# Core_Supply_Filter.net
KiCad netlist of a schematic drawn in Altium Designer
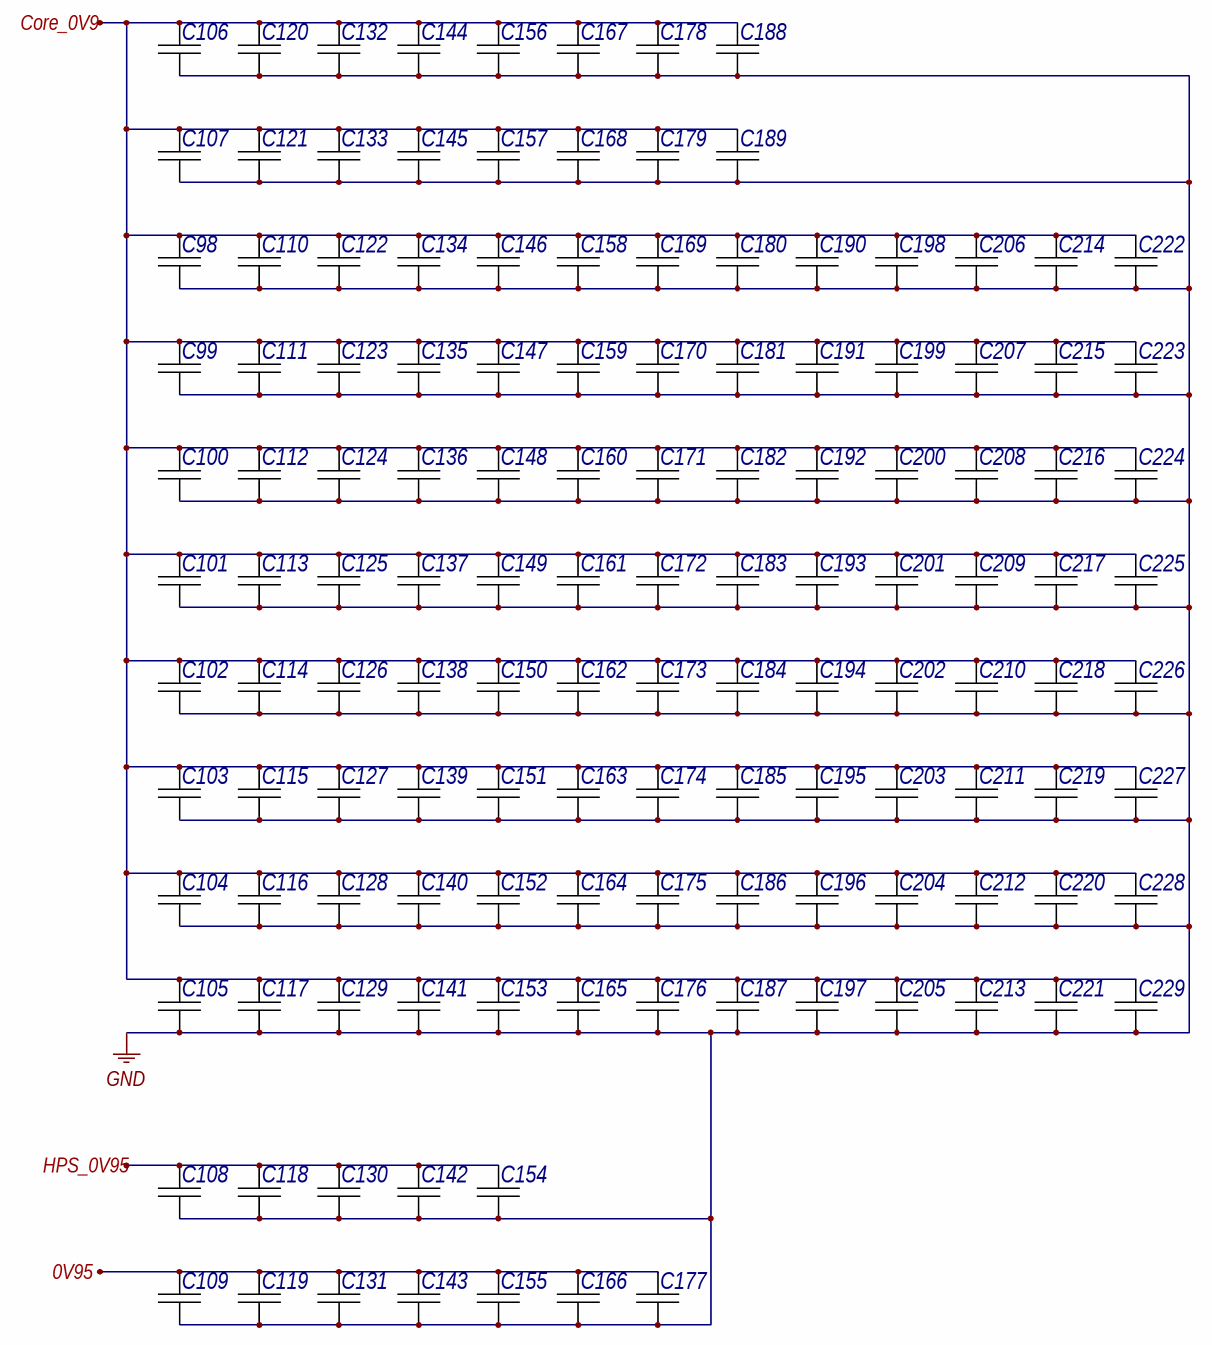
[diagram p0: Core Supply Filter.SchDoc]

(export (version "E")
  (design (tool "Eeschema 10.0.6"))
  (components
    (comp (ref "C98")
      (value "GRM033R60J104KE19D")
      (footprint "CAPC0603X33X15LL03T05")
      (description "Chip Capacitor, 100 nF, +/- 10%, 6.3 V, -55 to 85 degC, 0201 (0603 Metric), RoHS, Tape and Reel")
      (fields (field (name "TOLERANCE") "10%") (field (name "MANUFACTURER") "Basic Passives"))
      (libsource (lib "MiniPC DB") (part "CAP_NP"))
    )
    (comp (ref "C99")
      (value "GRM033R60J104KE19D")
      (footprint "CAPC0603X33X15LL03T05")
      (description "Chip Capacitor, 100 nF, +/- 10%, 6.3 V, -55 to 85 degC, 0201 (0603 Metric), RoHS, Tape and Reel")
      (fields (field (name "TOLERANCE") "10%") (field (name "MANUFACTURER") "Basic Passives"))
      (libsource (lib "MiniPC DB") (part "CAP_NP"))
    )
    (comp (ref "C100")
      (value "GRM033R60J104KE19D")
      (footprint "CAPC0603X33X15LL03T05")
      (description "Chip Capacitor, 100 nF, +/- 10%, 6.3 V, -55 to 85 degC, 0201 (0603 Metric), RoHS, Tape and Reel")
      (fields (field (name "TOLERANCE") "10%") (field (name "MANUFACTURER") "Basic Passives"))
      (libsource (lib "MiniPC DB") (part "CAP_NP"))
    )
    (comp (ref "C101")
      (value "GRM033R60J104KE19D")
      (footprint "CAPC0603X33X15LL03T05")
      (description "Chip Capacitor, 100 nF, +/- 10%, 6.3 V, -55 to 85 degC, 0201 (0603 Metric), RoHS, Tape and Reel")
      (fields (field (name "TOLERANCE") "10%") (field (name "MANUFACTURER") "Basic Passives"))
      (libsource (lib "MiniPC DB") (part "CAP_NP"))
    )
    (comp (ref "C102")
      (value "GRM033R60J104KE19D")
      (footprint "CAPC0603X33X15LL03T05")
      (description "Chip Capacitor, 100 nF, +/- 10%, 6.3 V, -55 to 85 degC, 0201 (0603 Metric), RoHS, Tape and Reel")
      (fields (field (name "TOLERANCE") "10%") (field (name "MANUFACTURER") "Basic Passives"))
      (libsource (lib "MiniPC DB") (part "CAP_NP"))
    )
    (comp (ref "C103")
      (value "GRM033R60J104KE19D")
      (footprint "CAPC0603X33X15LL03T05")
      (description "Chip Capacitor, 100 nF, +/- 10%, 6.3 V, -55 to 85 degC, 0201 (0603 Metric), RoHS, Tape and Reel")
      (fields (field (name "TOLERANCE") "10%") (field (name "MANUFACTURER") "Basic Passives"))
      (libsource (lib "MiniPC DB") (part "CAP_NP"))
    )
    (comp (ref "C104")
      (value "GRM033R60J104KE19D")
      (footprint "CAPC0603X33X15LL03T05")
      (description "Chip Capacitor, 100 nF, +/- 10%, 6.3 V, -55 to 85 degC, 0201 (0603 Metric), RoHS, Tape and Reel")
      (fields (field (name "TOLERANCE") "10%") (field (name "MANUFACTURER") "Basic Passives"))
      (libsource (lib "MiniPC DB") (part "CAP_NP"))
    )
    (comp (ref "C105")
      (value "GRM033R60J104KE19D")
      (footprint "CAPC0603X33X15LL03T05")
      (description "Chip Capacitor, 100 nF, +/- 10%, 6.3 V, -55 to 85 degC, 0201 (0603 Metric), RoHS, Tape and Reel")
      (fields (field (name "TOLERANCE") "10%") (field (name "MANUFACTURER") "Basic Passives"))
      (libsource (lib "MiniPC DB") (part "CAP_NP"))
    )
    (comp (ref "C106")
      (value "GRM31CR60J107ME39L")
      (footprint "CAPC3216X190X55ML30T25")
      (description "Chip Capacitor, 100 uF, +/- 20%, 6.3 V, -55 to 85 degC, 1206 (3216 Metric), RoHS, Tape and Reel")
      (fields (field (name "TOLERANCE") "20%"))
      (libsource (lib "MiniPC DB") (part "CAP_NP"))
    )
    (comp (ref "C107")
      (value "GRM31CR60J107ME39L")
      (footprint "CAPC3216X190X55ML30T25")
      (description "Chip Capacitor, 100 uF, +/- 20%, 6.3 V, -55 to 85 degC, 1206 (3216 Metric), RoHS, Tape and Reel")
      (fields (field (name "TOLERANCE") "20%"))
      (libsource (lib "MiniPC DB") (part "CAP_NP"))
    )
    (comp (ref "C108")
      (value "GRM31CR60J107ME39L")
      (footprint "CAPC3216X190X55ML30T25")
      (description "Chip Capacitor, 100 uF, +/- 20%, 6.3 V, -55 to 85 degC, 1206 (3216 Metric), RoHS, Tape and Reel")
      (fields (field (name "TOLERANCE") "20%"))
      (libsource (lib "MiniPC DB") (part "CAP_NP"))
    )
    (comp (ref "C109")
      (value "GRM31CR60J107ME39L")
      (footprint "CAPC3216X190X55ML30T25")
      (description "Chip Capacitor, 100 uF, +/- 20%, 6.3 V, -55 to 85 degC, 1206 (3216 Metric), RoHS, Tape and Reel")
      (fields (field (name "TOLERANCE") "20%"))
      (libsource (lib "MiniPC DB") (part "CAP_NP"))
    )
    (comp (ref "C110")
      (value "GRM033R60J104KE19D")
      (footprint "CAPC0603X33X15LL03T05")
      (description "Chip Capacitor, 100 nF, +/- 10%, 6.3 V, -55 to 85 degC, 0201 (0603 Metric), RoHS, Tape and Reel")
      (fields (field (name "TOLERANCE") "10%") (field (name "MANUFACTURER") "Basic Passives"))
      (libsource (lib "MiniPC DB") (part "CAP_NP"))
    )
    (comp (ref "C111")
      (value "GRM033R60J104KE19D")
      (footprint "CAPC0603X33X15LL03T05")
      (description "Chip Capacitor, 100 nF, +/- 10%, 6.3 V, -55 to 85 degC, 0201 (0603 Metric), RoHS, Tape and Reel")
      (fields (field (name "TOLERANCE") "10%") (field (name "MANUFACTURER") "Basic Passives"))
      (libsource (lib "MiniPC DB") (part "CAP_NP"))
    )
    (comp (ref "C112")
      (value "GRM033R60J104KE19D")
      (footprint "CAPC0603X33X15LL03T05")
      (description "Chip Capacitor, 100 nF, +/- 10%, 6.3 V, -55 to 85 degC, 0201 (0603 Metric), RoHS, Tape and Reel")
      (fields (field (name "TOLERANCE") "10%") (field (name "MANUFACTURER") "Basic Passives"))
      (libsource (lib "MiniPC DB") (part "CAP_NP"))
    )
    (comp (ref "C113")
      (value "GRM033R60J104KE19D")
      (footprint "CAPC0603X33X15LL03T05")
      (description "Chip Capacitor, 100 nF, +/- 10%, 6.3 V, -55 to 85 degC, 0201 (0603 Metric), RoHS, Tape and Reel")
      (fields (field (name "TOLERANCE") "10%") (field (name "MANUFACTURER") "Basic Passives"))
      (libsource (lib "MiniPC DB") (part "CAP_NP"))
    )
    (comp (ref "C114")
      (value "GRM033R60J104KE19D")
      (footprint "CAPC0603X33X15LL03T05")
      (description "Chip Capacitor, 100 nF, +/- 10%, 6.3 V, -55 to 85 degC, 0201 (0603 Metric), RoHS, Tape and Reel")
      (fields (field (name "TOLERANCE") "10%") (field (name "MANUFACTURER") "Basic Passives"))
      (libsource (lib "MiniPC DB") (part "CAP_NP"))
    )
    (comp (ref "C115")
      (value "GRM033R60J104KE19D")
      (footprint "CAPC0603X33X15LL03T05")
      (description "Chip Capacitor, 100 nF, +/- 10%, 6.3 V, -55 to 85 degC, 0201 (0603 Metric), RoHS, Tape and Reel")
      (fields (field (name "TOLERANCE") "10%") (field (name "MANUFACTURER") "Basic Passives"))
      (libsource (lib "MiniPC DB") (part "CAP_NP"))
    )
    (comp (ref "C116")
      (value "GRM033R60J104KE19D")
      (footprint "CAPC0603X33X15LL03T05")
      (description "Chip Capacitor, 100 nF, +/- 10%, 6.3 V, -55 to 85 degC, 0201 (0603 Metric), RoHS, Tape and Reel")
      (fields (field (name "TOLERANCE") "10%") (field (name "MANUFACTURER") "Basic Passives"))
      (libsource (lib "MiniPC DB") (part "CAP_NP"))
    )
    (comp (ref "C117")
      (value "GRM033R60J104KE19D")
      (footprint "CAPC0603X33X15LL03T05")
      (description "Chip Capacitor, 100 nF, +/- 10%, 6.3 V, -55 to 85 degC, 0201 (0603 Metric), RoHS, Tape and Reel")
      (fields (field (name "TOLERANCE") "10%") (field (name "MANUFACTURER") "Basic Passives"))
      (libsource (lib "MiniPC DB") (part "CAP_NP"))
    )
    (comp (ref "C118")
      (value "GRM033R60J104KE19D")
      (footprint "CAPC0603X33X15LL03T05")
      (description "Chip Capacitor, 100 nF, +/- 10%, 6.3 V, -55 to 85 degC, 0201 (0603 Metric), RoHS, Tape and Reel")
      (fields (field (name "TOLERANCE") "10%") (field (name "MANUFACTURER") "Basic Passives"))
      (libsource (lib "MiniPC DB") (part "CAP_NP"))
    )
    (comp (ref "C119")
      (value "GRM033R60J104KE19D")
      (footprint "CAPC0603X33X15LL03T05")
      (description "Chip Capacitor, 100 nF, +/- 10%, 6.3 V, -55 to 85 degC, 0201 (0603 Metric), RoHS, Tape and Reel")
      (fields (field (name "TOLERANCE") "10%") (field (name "MANUFACTURER") "Basic Passives"))
      (libsource (lib "MiniPC DB") (part "CAP_NP"))
    )
    (comp (ref "C120")
      (value "GRM31CR60J107ME39L")
      (footprint "CAPC3216X190X55ML30T25")
      (description "Chip Capacitor, 100 uF, +/- 20%, 6.3 V, -55 to 85 degC, 1206 (3216 Metric), RoHS, Tape and Reel")
      (fields (field (name "TOLERANCE") "20%"))
      (libsource (lib "MiniPC DB") (part "CAP_NP"))
    )
    (comp (ref "C121")
      (value "GRM31CR60J107ME39L")
      (footprint "CAPC3216X190X55ML30T25")
      (description "Chip Capacitor, 100 uF, +/- 20%, 6.3 V, -55 to 85 degC, 1206 (3216 Metric), RoHS, Tape and Reel")
      (fields (field (name "TOLERANCE") "20%"))
      (libsource (lib "MiniPC DB") (part "CAP_NP"))
    )
    (comp (ref "C122")
      (value "GRM033R60J104KE19D")
      (footprint "CAPC0603X33X15LL03T05")
      (description "Chip Capacitor, 100 nF, +/- 10%, 6.3 V, -55 to 85 degC, 0201 (0603 Metric), RoHS, Tape and Reel")
      (fields (field (name "TOLERANCE") "10%") (field (name "MANUFACTURER") "Basic Passives"))
      (libsource (lib "MiniPC DB") (part "CAP_NP"))
    )
    (comp (ref "C123")
      (value "GRM033R60J104KE19D")
      (footprint "CAPC0603X33X15LL03T05")
      (description "Chip Capacitor, 100 nF, +/- 10%, 6.3 V, -55 to 85 degC, 0201 (0603 Metric), RoHS, Tape and Reel")
      (fields (field (name "TOLERANCE") "10%") (field (name "MANUFACTURER") "Basic Passives"))
      (libsource (lib "MiniPC DB") (part "CAP_NP"))
    )
    (comp (ref "C124")
      (value "GRM033R60J104KE19D")
      (footprint "CAPC0603X33X15LL03T05")
      (description "Chip Capacitor, 100 nF, +/- 10%, 6.3 V, -55 to 85 degC, 0201 (0603 Metric), RoHS, Tape and Reel")
      (fields (field (name "TOLERANCE") "10%") (field (name "MANUFACTURER") "Basic Passives"))
      (libsource (lib "MiniPC DB") (part "CAP_NP"))
    )
    (comp (ref "C125")
      (value "GRM033R60J104KE19D")
      (footprint "CAPC0603X33X15LL03T05")
      (description "Chip Capacitor, 100 nF, +/- 10%, 6.3 V, -55 to 85 degC, 0201 (0603 Metric), RoHS, Tape and Reel")
      (fields (field (name "TOLERANCE") "10%") (field (name "MANUFACTURER") "Basic Passives"))
      (libsource (lib "MiniPC DB") (part "CAP_NP"))
    )
    (comp (ref "C126")
      (value "GRM033R60J104KE19D")
      (footprint "CAPC0603X33X15LL03T05")
      (description "Chip Capacitor, 100 nF, +/- 10%, 6.3 V, -55 to 85 degC, 0201 (0603 Metric), RoHS, Tape and Reel")
      (fields (field (name "TOLERANCE") "10%") (field (name "MANUFACTURER") "Basic Passives"))
      (libsource (lib "MiniPC DB") (part "CAP_NP"))
    )
    (comp (ref "C127")
      (value "GRM033R60J104KE19D")
      (footprint "CAPC0603X33X15LL03T05")
      (description "Chip Capacitor, 100 nF, +/- 10%, 6.3 V, -55 to 85 degC, 0201 (0603 Metric), RoHS, Tape and Reel")
      (fields (field (name "TOLERANCE") "10%") (field (name "MANUFACTURER") "Basic Passives"))
      (libsource (lib "MiniPC DB") (part "CAP_NP"))
    )
    (comp (ref "C128")
      (value "GRM033R60J104KE19D")
      (footprint "CAPC0603X33X15LL03T05")
      (description "Chip Capacitor, 100 nF, +/- 10%, 6.3 V, -55 to 85 degC, 0201 (0603 Metric), RoHS, Tape and Reel")
      (fields (field (name "TOLERANCE") "10%") (field (name "MANUFACTURER") "Basic Passives"))
      (libsource (lib "MiniPC DB") (part "CAP_NP"))
    )
    (comp (ref "C129")
      (value "GRM033R60J104KE19D")
      (footprint "CAPC0603X33X15LL03T05")
      (description "Chip Capacitor, 100 nF, +/- 10%, 6.3 V, -55 to 85 degC, 0201 (0603 Metric), RoHS, Tape and Reel")
      (fields (field (name "TOLERANCE") "10%") (field (name "MANUFACTURER") "Basic Passives"))
      (libsource (lib "MiniPC DB") (part "CAP_NP"))
    )
    (comp (ref "C130")
      (value "GRM033R60J104KE19D")
      (footprint "CAPC0603X33X15LL03T05")
      (description "Chip Capacitor, 100 nF, +/- 10%, 6.3 V, -55 to 85 degC, 0201 (0603 Metric), RoHS, Tape and Reel")
      (fields (field (name "TOLERANCE") "10%") (field (name "MANUFACTURER") "Basic Passives"))
      (libsource (lib "MiniPC DB") (part "CAP_NP"))
    )
    (comp (ref "C131")
      (value "GRM033R60J104KE19D")
      (footprint "CAPC0603X33X15LL03T05")
      (description "Chip Capacitor, 100 nF, +/- 10%, 6.3 V, -55 to 85 degC, 0201 (0603 Metric), RoHS, Tape and Reel")
      (fields (field (name "TOLERANCE") "10%") (field (name "MANUFACTURER") "Basic Passives"))
      (libsource (lib "MiniPC DB") (part "CAP_NP"))
    )
    (comp (ref "C132")
      (value "GRM31CR60J107ME39L")
      (footprint "CAPC3216X190X55ML30T25")
      (description "Chip Capacitor, 100 uF, +/- 20%, 6.3 V, -55 to 85 degC, 1206 (3216 Metric), RoHS, Tape and Reel")
      (fields (field (name "TOLERANCE") "20%"))
      (libsource (lib "MiniPC DB") (part "CAP_NP"))
    )
    (comp (ref "C133")
      (value "GRM31CR60J107ME39L")
      (footprint "CAPC3216X190X55ML30T25")
      (description "Chip Capacitor, 100 uF, +/- 20%, 6.3 V, -55 to 85 degC, 1206 (3216 Metric), RoHS, Tape and Reel")
      (fields (field (name "TOLERANCE") "20%"))
      (libsource (lib "MiniPC DB") (part "CAP_NP"))
    )
    (comp (ref "C134")
      (value "GRM033R60J104KE19D")
      (footprint "CAPC0603X33X15LL03T05")
      (description "Chip Capacitor, 100 nF, +/- 10%, 6.3 V, -55 to 85 degC, 0201 (0603 Metric), RoHS, Tape and Reel")
      (fields (field (name "TOLERANCE") "10%") (field (name "MANUFACTURER") "Basic Passives"))
      (libsource (lib "MiniPC DB") (part "CAP_NP"))
    )
    (comp (ref "C135")
      (value "GRM033R60J104KE19D")
      (footprint "CAPC0603X33X15LL03T05")
      (description "Chip Capacitor, 100 nF, +/- 10%, 6.3 V, -55 to 85 degC, 0201 (0603 Metric), RoHS, Tape and Reel")
      (fields (field (name "TOLERANCE") "10%") (field (name "MANUFACTURER") "Basic Passives"))
      (libsource (lib "MiniPC DB") (part "CAP_NP"))
    )
    (comp (ref "C136")
      (value "GRM033R60J104KE19D")
      (footprint "CAPC0603X33X15LL03T05")
      (description "Chip Capacitor, 100 nF, +/- 10%, 6.3 V, -55 to 85 degC, 0201 (0603 Metric), RoHS, Tape and Reel")
      (fields (field (name "TOLERANCE") "10%") (field (name "MANUFACTURER") "Basic Passives"))
      (libsource (lib "MiniPC DB") (part "CAP_NP"))
    )
    (comp (ref "C137")
      (value "GRM033R60J104KE19D")
      (footprint "CAPC0603X33X15LL03T05")
      (description "Chip Capacitor, 100 nF, +/- 10%, 6.3 V, -55 to 85 degC, 0201 (0603 Metric), RoHS, Tape and Reel")
      (fields (field (name "TOLERANCE") "10%") (field (name "MANUFACTURER") "Basic Passives"))
      (libsource (lib "MiniPC DB") (part "CAP_NP"))
    )
    (comp (ref "C138")
      (value "GRM033R60J104KE19D")
      (footprint "CAPC0603X33X15LL03T05")
      (description "Chip Capacitor, 100 nF, +/- 10%, 6.3 V, -55 to 85 degC, 0201 (0603 Metric), RoHS, Tape and Reel")
      (fields (field (name "TOLERANCE") "10%") (field (name "MANUFACTURER") "Basic Passives"))
      (libsource (lib "MiniPC DB") (part "CAP_NP"))
    )
    (comp (ref "C139")
      (value "GRM033R60J104KE19D")
      (footprint "CAPC0603X33X15LL03T05")
      (description "Chip Capacitor, 100 nF, +/- 10%, 6.3 V, -55 to 85 degC, 0201 (0603 Metric), RoHS, Tape and Reel")
      (fields (field (name "TOLERANCE") "10%") (field (name "MANUFACTURER") "Basic Passives"))
      (libsource (lib "MiniPC DB") (part "CAP_NP"))
    )
    (comp (ref "C140")
      (value "GRM033R60J104KE19D")
      (footprint "CAPC0603X33X15LL03T05")
      (description "Chip Capacitor, 100 nF, +/- 10%, 6.3 V, -55 to 85 degC, 0201 (0603 Metric), RoHS, Tape and Reel")
      (fields (field (name "TOLERANCE") "10%") (field (name "MANUFACTURER") "Basic Passives"))
      (libsource (lib "MiniPC DB") (part "CAP_NP"))
    )
    (comp (ref "C141")
      (value "GRM033R60J104KE19D")
      (footprint "CAPC0603X33X15LL03T05")
      (description "Chip Capacitor, 100 nF, +/- 10%, 6.3 V, -55 to 85 degC, 0201 (0603 Metric), RoHS, Tape and Reel")
      (fields (field (name "TOLERANCE") "10%") (field (name "MANUFACTURER") "Basic Passives"))
      (libsource (lib "MiniPC DB") (part "CAP_NP"))
    )
    (comp (ref "C142")
      (value "GRM033R60J104KE19D")
      (footprint "CAPC0603X33X15LL03T05")
      (description "Chip Capacitor, 100 nF, +/- 10%, 6.3 V, -55 to 85 degC, 0201 (0603 Metric), RoHS, Tape and Reel")
      (fields (field (name "TOLERANCE") "10%") (field (name "MANUFACTURER") "Basic Passives"))
      (libsource (lib "MiniPC DB") (part "CAP_NP"))
    )
    (comp (ref "C143")
      (value "GRM033R60J104KE19D")
      (footprint "CAPC0603X33X15LL03T05")
      (description "Chip Capacitor, 100 nF, +/- 10%, 6.3 V, -55 to 85 degC, 0201 (0603 Metric), RoHS, Tape and Reel")
      (fields (field (name "TOLERANCE") "10%") (field (name "MANUFACTURER") "Basic Passives"))
      (libsource (lib "MiniPC DB") (part "CAP_NP"))
    )
    (comp (ref "C144")
      (value "GRM31CR60J107ME39L")
      (footprint "CAPC3216X190X55ML30T25")
      (description "Chip Capacitor, 100 uF, +/- 20%, 6.3 V, -55 to 85 degC, 1206 (3216 Metric), RoHS, Tape and Reel")
      (fields (field (name "TOLERANCE") "20%"))
      (libsource (lib "MiniPC DB") (part "CAP_NP"))
    )
    (comp (ref "C145")
      (value "GRM31CR60J107ME39L")
      (footprint "CAPC3216X190X55ML30T25")
      (description "Chip Capacitor, 100 uF, +/- 20%, 6.3 V, -55 to 85 degC, 1206 (3216 Metric), RoHS, Tape and Reel")
      (fields (field (name "TOLERANCE") "20%"))
      (libsource (lib "MiniPC DB") (part "CAP_NP"))
    )
    (comp (ref "C146")
      (value "GRM033R60J104KE19D")
      (footprint "CAPC0603X33X15LL03T05")
      (description "Chip Capacitor, 100 nF, +/- 10%, 6.3 V, -55 to 85 degC, 0201 (0603 Metric), RoHS, Tape and Reel")
      (fields (field (name "TOLERANCE") "10%") (field (name "MANUFACTURER") "Basic Passives"))
      (libsource (lib "MiniPC DB") (part "CAP_NP"))
    )
    (comp (ref "C147")
      (value "GRM033R60J104KE19D")
      (footprint "CAPC0603X33X15LL03T05")
      (description "Chip Capacitor, 100 nF, +/- 10%, 6.3 V, -55 to 85 degC, 0201 (0603 Metric), RoHS, Tape and Reel")
      (fields (field (name "TOLERANCE") "10%") (field (name "MANUFACTURER") "Basic Passives"))
      (libsource (lib "MiniPC DB") (part "CAP_NP"))
    )
    (comp (ref "C148")
      (value "GRM033R60J104KE19D")
      (footprint "CAPC0603X33X15LL03T05")
      (description "Chip Capacitor, 100 nF, +/- 10%, 6.3 V, -55 to 85 degC, 0201 (0603 Metric), RoHS, Tape and Reel")
      (fields (field (name "TOLERANCE") "10%") (field (name "MANUFACTURER") "Basic Passives"))
      (libsource (lib "MiniPC DB") (part "CAP_NP"))
    )
    (comp (ref "C149")
      (value "GRM033R60J104KE19D")
      (footprint "CAPC0603X33X15LL03T05")
      (description "Chip Capacitor, 100 nF, +/- 10%, 6.3 V, -55 to 85 degC, 0201 (0603 Metric), RoHS, Tape and Reel")
      (fields (field (name "TOLERANCE") "10%") (field (name "MANUFACTURER") "Basic Passives"))
      (libsource (lib "MiniPC DB") (part "CAP_NP"))
    )
    (comp (ref "C150")
      (value "GRM033R60J104KE19D")
      (footprint "CAPC0603X33X15LL03T05")
      (description "Chip Capacitor, 100 nF, +/- 10%, 6.3 V, -55 to 85 degC, 0201 (0603 Metric), RoHS, Tape and Reel")
      (fields (field (name "TOLERANCE") "10%") (field (name "MANUFACTURER") "Basic Passives"))
      (libsource (lib "MiniPC DB") (part "CAP_NP"))
    )
    (comp (ref "C151")
      (value "GRM033R60J104KE19D")
      (footprint "CAPC0603X33X15LL03T05")
      (description "Chip Capacitor, 100 nF, +/- 10%, 6.3 V, -55 to 85 degC, 0201 (0603 Metric), RoHS, Tape and Reel")
      (fields (field (name "TOLERANCE") "10%") (field (name "MANUFACTURER") "Basic Passives"))
      (libsource (lib "MiniPC DB") (part "CAP_NP"))
    )
    (comp (ref "C152")
      (value "GRM033R60J104KE19D")
      (footprint "CAPC0603X33X15LL03T05")
      (description "Chip Capacitor, 100 nF, +/- 10%, 6.3 V, -55 to 85 degC, 0201 (0603 Metric), RoHS, Tape and Reel")
      (fields (field (name "TOLERANCE") "10%") (field (name "MANUFACTURER") "Basic Passives"))
      (libsource (lib "MiniPC DB") (part "CAP_NP"))
    )
    (comp (ref "C153")
      (value "GRM033R60J104KE19D")
      (footprint "CAPC0603X33X15LL03T05")
      (description "Chip Capacitor, 100 nF, +/- 10%, 6.3 V, -55 to 85 degC, 0201 (0603 Metric), RoHS, Tape and Reel")
      (fields (field (name "TOLERANCE") "10%") (field (name "MANUFACTURER") "Basic Passives"))
      (libsource (lib "MiniPC DB") (part "CAP_NP"))
    )
    (comp (ref "C154")
      (value "GRM033R60J104KE19D")
      (footprint "CAPC0603X33X15LL03T05")
      (description "Chip Capacitor, 100 nF, +/- 10%, 6.3 V, -55 to 85 degC, 0201 (0603 Metric), RoHS, Tape and Reel")
      (fields (field (name "TOLERANCE") "10%") (field (name "MANUFACTURER") "Basic Passives"))
      (libsource (lib "MiniPC DB") (part "CAP_NP"))
    )
    (comp (ref "C155")
      (value "GRM033R60J104KE19D")
      (footprint "CAPC0603X33X15LL03T05")
      (description "Chip Capacitor, 100 nF, +/- 10%, 6.3 V, -55 to 85 degC, 0201 (0603 Metric), RoHS, Tape and Reel")
      (fields (field (name "TOLERANCE") "10%") (field (name "MANUFACTURER") "Basic Passives"))
      (libsource (lib "MiniPC DB") (part "CAP_NP"))
    )
    (comp (ref "C156")
      (value "GRM31CR60J107ME39L")
      (footprint "CAPC3216X190X55ML30T25")
      (description "Chip Capacitor, 100 uF, +/- 20%, 6.3 V, -55 to 85 degC, 1206 (3216 Metric), RoHS, Tape and Reel")
      (fields (field (name "TOLERANCE") "20%"))
      (libsource (lib "MiniPC DB") (part "CAP_NP"))
    )
    (comp (ref "C157")
      (value "GRM31CR60J107ME39L")
      (footprint "CAPC3216X190X55ML30T25")
      (description "Chip Capacitor, 100 uF, +/- 20%, 6.3 V, -55 to 85 degC, 1206 (3216 Metric), RoHS, Tape and Reel")
      (fields (field (name "TOLERANCE") "20%"))
      (libsource (lib "MiniPC DB") (part "CAP_NP"))
    )
    (comp (ref "C158")
      (value "GRM033R60J104KE19D")
      (footprint "CAPC0603X33X15LL03T05")
      (description "Chip Capacitor, 100 nF, +/- 10%, 6.3 V, -55 to 85 degC, 0201 (0603 Metric), RoHS, Tape and Reel")
      (fields (field (name "TOLERANCE") "10%") (field (name "MANUFACTURER") "Basic Passives"))
      (libsource (lib "MiniPC DB") (part "CAP_NP"))
    )
    (comp (ref "C159")
      (value "GRM033R60J104KE19D")
      (footprint "CAPC0603X33X15LL03T05")
      (description "Chip Capacitor, 100 nF, +/- 10%, 6.3 V, -55 to 85 degC, 0201 (0603 Metric), RoHS, Tape and Reel")
      (fields (field (name "TOLERANCE") "10%") (field (name "MANUFACTURER") "Basic Passives"))
      (libsource (lib "MiniPC DB") (part "CAP_NP"))
    )
    (comp (ref "C160")
      (value "GRM033R60J104KE19D")
      (footprint "CAPC0603X33X15LL03T05")
      (description "Chip Capacitor, 100 nF, +/- 10%, 6.3 V, -55 to 85 degC, 0201 (0603 Metric), RoHS, Tape and Reel")
      (fields (field (name "TOLERANCE") "10%") (field (name "MANUFACTURER") "Basic Passives"))
      (libsource (lib "MiniPC DB") (part "CAP_NP"))
    )
    (comp (ref "C161")
      (value "GRM033R60J104KE19D")
      (footprint "CAPC0603X33X15LL03T05")
      (description "Chip Capacitor, 100 nF, +/- 10%, 6.3 V, -55 to 85 degC, 0201 (0603 Metric), RoHS, Tape and Reel")
      (fields (field (name "TOLERANCE") "10%") (field (name "MANUFACTURER") "Basic Passives"))
      (libsource (lib "MiniPC DB") (part "CAP_NP"))
    )
    (comp (ref "C162")
      (value "GRM033R60J104KE19D")
      (footprint "CAPC0603X33X15LL03T05")
      (description "Chip Capacitor, 100 nF, +/- 10%, 6.3 V, -55 to 85 degC, 0201 (0603 Metric), RoHS, Tape and Reel")
      (fields (field (name "TOLERANCE") "10%") (field (name "MANUFACTURER") "Basic Passives"))
      (libsource (lib "MiniPC DB") (part "CAP_NP"))
    )
    (comp (ref "C163")
      (value "GRM033R60J104KE19D")
      (footprint "CAPC0603X33X15LL03T05")
      (description "Chip Capacitor, 100 nF, +/- 10%, 6.3 V, -55 to 85 degC, 0201 (0603 Metric), RoHS, Tape and Reel")
      (fields (field (name "TOLERANCE") "10%") (field (name "MANUFACTURER") "Basic Passives"))
      (libsource (lib "MiniPC DB") (part "CAP_NP"))
    )
    (comp (ref "C164")
      (value "GRM033R60J104KE19D")
      (footprint "CAPC0603X33X15LL03T05")
      (description "Chip Capacitor, 100 nF, +/- 10%, 6.3 V, -55 to 85 degC, 0201 (0603 Metric), RoHS, Tape and Reel")
      (fields (field (name "TOLERANCE") "10%") (field (name "MANUFACTURER") "Basic Passives"))
      (libsource (lib "MiniPC DB") (part "CAP_NP"))
    )
    (comp (ref "C165")
      (value "GRM033R60J104KE19D")
      (footprint "CAPC0603X33X15LL03T05")
      (description "Chip Capacitor, 100 nF, +/- 10%, 6.3 V, -55 to 85 degC, 0201 (0603 Metric), RoHS, Tape and Reel")
      (fields (field (name "TOLERANCE") "10%") (field (name "MANUFACTURER") "Basic Passives"))
      (libsource (lib "MiniPC DB") (part "CAP_NP"))
    )
    (comp (ref "C166")
      (value "GRM033R60J104KE19D")
      (footprint "CAPC0603X33X15LL03T05")
      (description "Chip Capacitor, 100 nF, +/- 10%, 6.3 V, -55 to 85 degC, 0201 (0603 Metric), RoHS, Tape and Reel")
      (fields (field (name "TOLERANCE") "10%") (field (name "MANUFACTURER") "Basic Passives"))
      (libsource (lib "MiniPC DB") (part "CAP_NP"))
    )
    (comp (ref "C167")
      (value "GRM31CR60J107ME39L")
      (footprint "CAPC3216X190X55ML30T25")
      (description "Chip Capacitor, 100 uF, +/- 20%, 6.3 V, -55 to 85 degC, 1206 (3216 Metric), RoHS, Tape and Reel")
      (fields (field (name "TOLERANCE") "20%"))
      (libsource (lib "MiniPC DB") (part "CAP_NP"))
    )
    (comp (ref "C168")
      (value "GRM31CR60J107ME39L")
      (footprint "CAPC3216X190X55ML30T25")
      (description "Chip Capacitor, 100 uF, +/- 20%, 6.3 V, -55 to 85 degC, 1206 (3216 Metric), RoHS, Tape and Reel")
      (fields (field (name "TOLERANCE") "20%"))
      (libsource (lib "MiniPC DB") (part "CAP_NP"))
    )
    (comp (ref "C169")
      (value "GRM033R60J104KE19D")
      (footprint "CAPC0603X33X15LL03T05")
      (description "Chip Capacitor, 100 nF, +/- 10%, 6.3 V, -55 to 85 degC, 0201 (0603 Metric), RoHS, Tape and Reel")
      (fields (field (name "TOLERANCE") "10%") (field (name "MANUFACTURER") "Basic Passives"))
      (libsource (lib "MiniPC DB") (part "CAP_NP"))
    )
    (comp (ref "C170")
      (value "GRM033R60J104KE19D")
      (footprint "CAPC0603X33X15LL03T05")
      (description "Chip Capacitor, 100 nF, +/- 10%, 6.3 V, -55 to 85 degC, 0201 (0603 Metric), RoHS, Tape and Reel")
      (fields (field (name "TOLERANCE") "10%") (field (name "MANUFACTURER") "Basic Passives"))
      (libsource (lib "MiniPC DB") (part "CAP_NP"))
    )
    (comp (ref "C171")
      (value "GRM033R60J104KE19D")
      (footprint "CAPC0603X33X15LL03T05")
      (description "Chip Capacitor, 100 nF, +/- 10%, 6.3 V, -55 to 85 degC, 0201 (0603 Metric), RoHS, Tape and Reel")
      (fields (field (name "TOLERANCE") "10%") (field (name "MANUFACTURER") "Basic Passives"))
      (libsource (lib "MiniPC DB") (part "CAP_NP"))
    )
    (comp (ref "C172")
      (value "GRM033R60J104KE19D")
      (footprint "CAPC0603X33X15LL03T05")
      (description "Chip Capacitor, 100 nF, +/- 10%, 6.3 V, -55 to 85 degC, 0201 (0603 Metric), RoHS, Tape and Reel")
      (fields (field (name "TOLERANCE") "10%") (field (name "MANUFACTURER") "Basic Passives"))
      (libsource (lib "MiniPC DB") (part "CAP_NP"))
    )
    (comp (ref "C173")
      (value "GRM033R60J104KE19D")
      (footprint "CAPC0603X33X15LL03T05")
      (description "Chip Capacitor, 100 nF, +/- 10%, 6.3 V, -55 to 85 degC, 0201 (0603 Metric), RoHS, Tape and Reel")
      (fields (field (name "TOLERANCE") "10%") (field (name "MANUFACTURER") "Basic Passives"))
      (libsource (lib "MiniPC DB") (part "CAP_NP"))
    )
    (comp (ref "C174")
      (value "GRM033R60J104KE19D")
      (footprint "CAPC0603X33X15LL03T05")
      (description "Chip Capacitor, 100 nF, +/- 10%, 6.3 V, -55 to 85 degC, 0201 (0603 Metric), RoHS, Tape and Reel")
      (fields (field (name "TOLERANCE") "10%") (field (name "MANUFACTURER") "Basic Passives"))
      (libsource (lib "MiniPC DB") (part "CAP_NP"))
    )
    (comp (ref "C175")
      (value "GRM033R60J104KE19D")
      (footprint "CAPC0603X33X15LL03T05")
      (description "Chip Capacitor, 100 nF, +/- 10%, 6.3 V, -55 to 85 degC, 0201 (0603 Metric), RoHS, Tape and Reel")
      (fields (field (name "TOLERANCE") "10%") (field (name "MANUFACTURER") "Basic Passives"))
      (libsource (lib "MiniPC DB") (part "CAP_NP"))
    )
    (comp (ref "C176")
      (value "GRM033R60J104KE19D")
      (footprint "CAPC0603X33X15LL03T05")
      (description "Chip Capacitor, 100 nF, +/- 10%, 6.3 V, -55 to 85 degC, 0201 (0603 Metric), RoHS, Tape and Reel")
      (fields (field (name "TOLERANCE") "10%") (field (name "MANUFACTURER") "Basic Passives"))
      (libsource (lib "MiniPC DB") (part "CAP_NP"))
    )
    (comp (ref "C177")
      (value "GRM033R60J104KE19D")
      (footprint "CAPC0603X33X15LL03T05")
      (description "Chip Capacitor, 100 nF, +/- 10%, 6.3 V, -55 to 85 degC, 0201 (0603 Metric), RoHS, Tape and Reel")
      (fields (field (name "TOLERANCE") "10%") (field (name "MANUFACTURER") "Basic Passives"))
      (libsource (lib "MiniPC DB") (part "CAP_NP"))
    )
    (comp (ref "C178")
      (value "GRM31CR60J107ME39L")
      (footprint "CAPC3216X190X55ML30T25")
      (description "Chip Capacitor, 100 uF, +/- 20%, 6.3 V, -55 to 85 degC, 1206 (3216 Metric), RoHS, Tape and Reel")
      (fields (field (name "TOLERANCE") "20%"))
      (libsource (lib "MiniPC DB") (part "CAP_NP"))
    )
    (comp (ref "C179")
      (value "GRM31CR60J107ME39L")
      (footprint "CAPC3216X190X55ML30T25")
      (description "Chip Capacitor, 100 uF, +/- 20%, 6.3 V, -55 to 85 degC, 1206 (3216 Metric), RoHS, Tape and Reel")
      (fields (field (name "TOLERANCE") "20%"))
      (libsource (lib "MiniPC DB") (part "CAP_NP"))
    )
    (comp (ref "C180")
      (value "GRM033R60J104KE19D")
      (footprint "CAPC0603X33X15LL03T05")
      (description "Chip Capacitor, 100 nF, +/- 10%, 6.3 V, -55 to 85 degC, 0201 (0603 Metric), RoHS, Tape and Reel")
      (fields (field (name "TOLERANCE") "10%") (field (name "MANUFACTURER") "Basic Passives"))
      (libsource (lib "MiniPC DB") (part "CAP_NP"))
    )
    (comp (ref "C181")
      (value "GRM033R60J104KE19D")
      (footprint "CAPC0603X33X15LL03T05")
      (description "Chip Capacitor, 100 nF, +/- 10%, 6.3 V, -55 to 85 degC, 0201 (0603 Metric), RoHS, Tape and Reel")
      (fields (field (name "TOLERANCE") "10%") (field (name "MANUFACTURER") "Basic Passives"))
      (libsource (lib "MiniPC DB") (part "CAP_NP"))
    )
    (comp (ref "C182")
      (value "GRM033R60J104KE19D")
      (footprint "CAPC0603X33X15LL03T05")
      (description "Chip Capacitor, 100 nF, +/- 10%, 6.3 V, -55 to 85 degC, 0201 (0603 Metric), RoHS, Tape and Reel")
      (fields (field (name "TOLERANCE") "10%") (field (name "MANUFACTURER") "Basic Passives"))
      (libsource (lib "MiniPC DB") (part "CAP_NP"))
    )
    (comp (ref "C183")
      (value "GRM033R60J104KE19D")
      (footprint "CAPC0603X33X15LL03T05")
      (description "Chip Capacitor, 100 nF, +/- 10%, 6.3 V, -55 to 85 degC, 0201 (0603 Metric), RoHS, Tape and Reel")
      (fields (field (name "TOLERANCE") "10%") (field (name "MANUFACTURER") "Basic Passives"))
      (libsource (lib "MiniPC DB") (part "CAP_NP"))
    )
    (comp (ref "C184")
      (value "GRM033R60J104KE19D")
      (footprint "CAPC0603X33X15LL03T05")
      (description "Chip Capacitor, 100 nF, +/- 10%, 6.3 V, -55 to 85 degC, 0201 (0603 Metric), RoHS, Tape and Reel")
      (fields (field (name "TOLERANCE") "10%") (field (name "MANUFACTURER") "Basic Passives"))
      (libsource (lib "MiniPC DB") (part "CAP_NP"))
    )
    (comp (ref "C185")
      (value "GRM033R60J104KE19D")
      (footprint "CAPC0603X33X15LL03T05")
      (description "Chip Capacitor, 100 nF, +/- 10%, 6.3 V, -55 to 85 degC, 0201 (0603 Metric), RoHS, Tape and Reel")
      (fields (field (name "TOLERANCE") "10%") (field (name "MANUFACTURER") "Basic Passives"))
      (libsource (lib "MiniPC DB") (part "CAP_NP"))
    )
    (comp (ref "C186")
      (value "GRM033R60J104KE19D")
      (footprint "CAPC0603X33X15LL03T05")
      (description "Chip Capacitor, 100 nF, +/- 10%, 6.3 V, -55 to 85 degC, 0201 (0603 Metric), RoHS, Tape and Reel")
      (fields (field (name "TOLERANCE") "10%") (field (name "MANUFACTURER") "Basic Passives"))
      (libsource (lib "MiniPC DB") (part "CAP_NP"))
    )
    (comp (ref "C187")
      (value "GRM033R60J104KE19D")
      (footprint "CAPC0603X33X15LL03T05")
      (description "Chip Capacitor, 100 nF, +/- 10%, 6.3 V, -55 to 85 degC, 0201 (0603 Metric), RoHS, Tape and Reel")
      (fields (field (name "TOLERANCE") "10%") (field (name "MANUFACTURER") "Basic Passives"))
      (libsource (lib "MiniPC DB") (part "CAP_NP"))
    )
    (comp (ref "C188")
      (value "GRM31CR60J107ME39L")
      (footprint "CAPC3216X190X55ML30T25")
      (description "Chip Capacitor, 100 uF, +/- 20%, 6.3 V, -55 to 85 degC, 1206 (3216 Metric), RoHS, Tape and Reel")
      (fields (field (name "TOLERANCE") "20%"))
      (libsource (lib "MiniPC DB") (part "CAP_NP"))
    )
    (comp (ref "C189")
      (value "GRM31CR60J107ME39L")
      (footprint "CAPC3216X190X55ML30T25")
      (description "Chip Capacitor, 100 uF, +/- 20%, 6.3 V, -55 to 85 degC, 1206 (3216 Metric), RoHS, Tape and Reel")
      (fields (field (name "TOLERANCE") "20%"))
      (libsource (lib "MiniPC DB") (part "CAP_NP"))
    )
    (comp (ref "C190")
      (value "GRM033R60J104KE19D")
      (footprint "CAPC0603X33X15LL03T05")
      (description "Chip Capacitor, 100 nF, +/- 10%, 6.3 V, -55 to 85 degC, 0201 (0603 Metric), RoHS, Tape and Reel")
      (fields (field (name "TOLERANCE") "10%") (field (name "MANUFACTURER") "Basic Passives"))
      (libsource (lib "MiniPC DB") (part "CAP_NP"))
    )
    (comp (ref "C191")
      (value "GRM033R60J104KE19D")
      (footprint "CAPC0603X33X15LL03T05")
      (description "Chip Capacitor, 100 nF, +/- 10%, 6.3 V, -55 to 85 degC, 0201 (0603 Metric), RoHS, Tape and Reel")
      (fields (field (name "TOLERANCE") "10%") (field (name "MANUFACTURER") "Basic Passives"))
      (libsource (lib "MiniPC DB") (part "CAP_NP"))
    )
    (comp (ref "C192")
      (value "GRM033R60J104KE19D")
      (footprint "CAPC0603X33X15LL03T05")
      (description "Chip Capacitor, 100 nF, +/- 10%, 6.3 V, -55 to 85 degC, 0201 (0603 Metric), RoHS, Tape and Reel")
      (fields (field (name "TOLERANCE") "10%") (field (name "MANUFACTURER") "Basic Passives"))
      (libsource (lib "MiniPC DB") (part "CAP_NP"))
    )
    (comp (ref "C193")
      (value "GRM033R60J104KE19D")
      (footprint "CAPC0603X33X15LL03T05")
      (description "Chip Capacitor, 100 nF, +/- 10%, 6.3 V, -55 to 85 degC, 0201 (0603 Metric), RoHS, Tape and Reel")
      (fields (field (name "TOLERANCE") "10%") (field (name "MANUFACTURER") "Basic Passives"))
      (libsource (lib "MiniPC DB") (part "CAP_NP"))
    )
    (comp (ref "C194")
      (value "GRM033R60J104KE19D")
      (footprint "CAPC0603X33X15LL03T05")
      (description "Chip Capacitor, 100 nF, +/- 10%, 6.3 V, -55 to 85 degC, 0201 (0603 Metric), RoHS, Tape and Reel")
      (fields (field (name "TOLERANCE") "10%") (field (name "MANUFACTURER") "Basic Passives"))
      (libsource (lib "MiniPC DB") (part "CAP_NP"))
    )
    (comp (ref "C195")
      (value "GRM033R60J104KE19D")
      (footprint "CAPC0603X33X15LL03T05")
      (description "Chip Capacitor, 100 nF, +/- 10%, 6.3 V, -55 to 85 degC, 0201 (0603 Metric), RoHS, Tape and Reel")
      (fields (field (name "TOLERANCE") "10%") (field (name "MANUFACTURER") "Basic Passives"))
      (libsource (lib "MiniPC DB") (part "CAP_NP"))
    )
    (comp (ref "C196")
      (value "GRM033R60J104KE19D")
      (footprint "CAPC0603X33X15LL03T05")
      (description "Chip Capacitor, 100 nF, +/- 10%, 6.3 V, -55 to 85 degC, 0201 (0603 Metric), RoHS, Tape and Reel")
      (fields (field (name "TOLERANCE") "10%") (field (name "MANUFACTURER") "Basic Passives"))
      (libsource (lib "MiniPC DB") (part "CAP_NP"))
    )
    (comp (ref "C197")
      (value "GRM033R60J104KE19D")
      (footprint "CAPC0603X33X15LL03T05")
      (description "Chip Capacitor, 100 nF, +/- 10%, 6.3 V, -55 to 85 degC, 0201 (0603 Metric), RoHS, Tape and Reel")
      (fields (field (name "TOLERANCE") "10%") (field (name "MANUFACTURER") "Basic Passives"))
      (libsource (lib "MiniPC DB") (part "CAP_NP"))
    )
    (comp (ref "C198")
      (value "GRM033R60J104KE19D")
      (footprint "CAPC0603X33X15LL03T05")
      (description "Chip Capacitor, 100 nF, +/- 10%, 6.3 V, -55 to 85 degC, 0201 (0603 Metric), RoHS, Tape and Reel")
      (fields (field (name "TOLERANCE") "10%") (field (name "MANUFACTURER") "Basic Passives"))
      (libsource (lib "MiniPC DB") (part "CAP_NP"))
    )
    (comp (ref "C199")
      (value "GRM033R60J104KE19D")
      (footprint "CAPC0603X33X15LL03T05")
      (description "Chip Capacitor, 100 nF, +/- 10%, 6.3 V, -55 to 85 degC, 0201 (0603 Metric), RoHS, Tape and Reel")
      (fields (field (name "TOLERANCE") "10%") (field (name "MANUFACTURER") "Basic Passives"))
      (libsource (lib "MiniPC DB") (part "CAP_NP"))
    )
    (comp (ref "C200")
      (value "GRM033R60J104KE19D")
      (footprint "CAPC0603X33X15LL03T05")
      (description "Chip Capacitor, 100 nF, +/- 10%, 6.3 V, -55 to 85 degC, 0201 (0603 Metric), RoHS, Tape and Reel")
      (fields (field (name "TOLERANCE") "10%") (field (name "MANUFACTURER") "Basic Passives"))
      (libsource (lib "MiniPC DB") (part "CAP_NP"))
    )
    (comp (ref "C201")
      (value "GRM033R60J104KE19D")
      (footprint "CAPC0603X33X15LL03T05")
      (description "Chip Capacitor, 100 nF, +/- 10%, 6.3 V, -55 to 85 degC, 0201 (0603 Metric), RoHS, Tape and Reel")
      (fields (field (name "TOLERANCE") "10%") (field (name "MANUFACTURER") "Basic Passives"))
      (libsource (lib "MiniPC DB") (part "CAP_NP"))
    )
    (comp (ref "C202")
      (value "GRM033R60J104KE19D")
      (footprint "CAPC0603X33X15LL03T05")
      (description "Chip Capacitor, 100 nF, +/- 10%, 6.3 V, -55 to 85 degC, 0201 (0603 Metric), RoHS, Tape and Reel")
      (fields (field (name "TOLERANCE") "10%") (field (name "MANUFACTURER") "Basic Passives"))
      (libsource (lib "MiniPC DB") (part "CAP_NP"))
    )
    (comp (ref "C203")
      (value "GRM033R60J104KE19D")
      (footprint "CAPC0603X33X15LL03T05")
      (description "Chip Capacitor, 100 nF, +/- 10%, 6.3 V, -55 to 85 degC, 0201 (0603 Metric), RoHS, Tape and Reel")
      (fields (field (name "TOLERANCE") "10%") (field (name "MANUFACTURER") "Basic Passives"))
      (libsource (lib "MiniPC DB") (part "CAP_NP"))
    )
    (comp (ref "C204")
      (value "GRM033R60J104KE19D")
      (footprint "CAPC0603X33X15LL03T05")
      (description "Chip Capacitor, 100 nF, +/- 10%, 6.3 V, -55 to 85 degC, 0201 (0603 Metric), RoHS, Tape and Reel")
      (fields (field (name "TOLERANCE") "10%") (field (name "MANUFACTURER") "Basic Passives"))
      (libsource (lib "MiniPC DB") (part "CAP_NP"))
    )
    (comp (ref "C205")
      (value "GRM033R60J104KE19D")
      (footprint "CAPC0603X33X15LL03T05")
      (description "Chip Capacitor, 100 nF, +/- 10%, 6.3 V, -55 to 85 degC, 0201 (0603 Metric), RoHS, Tape and Reel")
      (fields (field (name "TOLERANCE") "10%") (field (name "MANUFACTURER") "Basic Passives"))
      (libsource (lib "MiniPC DB") (part "CAP_NP"))
    )
    (comp (ref "C206")
      (value "GRM033R60J104KE19D")
      (footprint "CAPC0603X33X15LL03T05")
      (description "Chip Capacitor, 100 nF, +/- 10%, 6.3 V, -55 to 85 degC, 0201 (0603 Metric), RoHS, Tape and Reel")
      (fields (field (name "TOLERANCE") "10%") (field (name "MANUFACTURER") "Basic Passives"))
      (libsource (lib "MiniPC DB") (part "CAP_NP"))
    )
    (comp (ref "C207")
      (value "GRM033R60J104KE19D")
      (footprint "CAPC0603X33X15LL03T05")
      (description "Chip Capacitor, 100 nF, +/- 10%, 6.3 V, -55 to 85 degC, 0201 (0603 Metric), RoHS, Tape and Reel")
      (fields (field (name "TOLERANCE") "10%") (field (name "MANUFACTURER") "Basic Passives"))
      (libsource (lib "MiniPC DB") (part "CAP_NP"))
    )
    (comp (ref "C208")
      (value "GRM033R60J104KE19D")
      (footprint "CAPC0603X33X15LL03T05")
      (description "Chip Capacitor, 100 nF, +/- 10%, 6.3 V, -55 to 85 degC, 0201 (0603 Metric), RoHS, Tape and Reel")
      (fields (field (name "TOLERANCE") "10%") (field (name "MANUFACTURER") "Basic Passives"))
      (libsource (lib "MiniPC DB") (part "CAP_NP"))
    )
    (comp (ref "C209")
      (value "GRM033R60J104KE19D")
      (footprint "CAPC0603X33X15LL03T05")
      (description "Chip Capacitor, 100 nF, +/- 10%, 6.3 V, -55 to 85 degC, 0201 (0603 Metric), RoHS, Tape and Reel")
      (fields (field (name "TOLERANCE") "10%") (field (name "MANUFACTURER") "Basic Passives"))
      (libsource (lib "MiniPC DB") (part "CAP_NP"))
    )
    (comp (ref "C210")
      (value "GRM033R60J104KE19D")
      (footprint "CAPC0603X33X15LL03T05")
      (description "Chip Capacitor, 100 nF, +/- 10%, 6.3 V, -55 to 85 degC, 0201 (0603 Metric), RoHS, Tape and Reel")
      (fields (field (name "TOLERANCE") "10%") (field (name "MANUFACTURER") "Basic Passives"))
      (libsource (lib "MiniPC DB") (part "CAP_NP"))
    )
    (comp (ref "C211")
      (value "GRM033R60J104KE19D")
      (footprint "CAPC0603X33X15LL03T05")
      (description "Chip Capacitor, 100 nF, +/- 10%, 6.3 V, -55 to 85 degC, 0201 (0603 Metric), RoHS, Tape and Reel")
      (fields (field (name "TOLERANCE") "10%") (field (name "MANUFACTURER") "Basic Passives"))
      (libsource (lib "MiniPC DB") (part "CAP_NP"))
    )
    (comp (ref "C212")
      (value "GRM033R60J104KE19D")
      (footprint "CAPC0603X33X15LL03T05")
      (description "Chip Capacitor, 100 nF, +/- 10%, 6.3 V, -55 to 85 degC, 0201 (0603 Metric), RoHS, Tape and Reel")
      (fields (field (name "TOLERANCE") "10%") (field (name "MANUFACTURER") "Basic Passives"))
      (libsource (lib "MiniPC DB") (part "CAP_NP"))
    )
    (comp (ref "C213")
      (value "GRM033R60J104KE19D")
      (footprint "CAPC0603X33X15LL03T05")
      (description "Chip Capacitor, 100 nF, +/- 10%, 6.3 V, -55 to 85 degC, 0201 (0603 Metric), RoHS, Tape and Reel")
      (fields (field (name "TOLERANCE") "10%") (field (name "MANUFACTURER") "Basic Passives"))
      (libsource (lib "MiniPC DB") (part "CAP_NP"))
    )
    (comp (ref "C214")
      (value "GRM033R60J104KE19D")
      (footprint "CAPC0603X33X15LL03T05")
      (description "Chip Capacitor, 100 nF, +/- 10%, 6.3 V, -55 to 85 degC, 0201 (0603 Metric), RoHS, Tape and Reel")
      (fields (field (name "TOLERANCE") "10%") (field (name "MANUFACTURER") "Basic Passives"))
      (libsource (lib "MiniPC DB") (part "CAP_NP"))
    )
    (comp (ref "C215")
      (value "GRM033R60J104KE19D")
      (footprint "CAPC0603X33X15LL03T05")
      (description "Chip Capacitor, 100 nF, +/- 10%, 6.3 V, -55 to 85 degC, 0201 (0603 Metric), RoHS, Tape and Reel")
      (fields (field (name "TOLERANCE") "10%") (field (name "MANUFACTURER") "Basic Passives"))
      (libsource (lib "MiniPC DB") (part "CAP_NP"))
    )
    (comp (ref "C216")
      (value "GRM033R60J104KE19D")
      (footprint "CAPC0603X33X15LL03T05")
      (description "Chip Capacitor, 100 nF, +/- 10%, 6.3 V, -55 to 85 degC, 0201 (0603 Metric), RoHS, Tape and Reel")
      (fields (field (name "TOLERANCE") "10%") (field (name "MANUFACTURER") "Basic Passives"))
      (libsource (lib "MiniPC DB") (part "CAP_NP"))
    )
    (comp (ref "C217")
      (value "GRM033R60J104KE19D")
      (footprint "CAPC0603X33X15LL03T05")
      (description "Chip Capacitor, 100 nF, +/- 10%, 6.3 V, -55 to 85 degC, 0201 (0603 Metric), RoHS, Tape and Reel")
      (fields (field (name "TOLERANCE") "10%") (field (name "MANUFACTURER") "Basic Passives"))
      (libsource (lib "MiniPC DB") (part "CAP_NP"))
    )
    (comp (ref "C218")
      (value "GRM033R60J104KE19D")
      (footprint "CAPC0603X33X15LL03T05")
      (description "Chip Capacitor, 100 nF, +/- 10%, 6.3 V, -55 to 85 degC, 0201 (0603 Metric), RoHS, Tape and Reel")
      (fields (field (name "TOLERANCE") "10%") (field (name "MANUFACTURER") "Basic Passives"))
      (libsource (lib "MiniPC DB") (part "CAP_NP"))
    )
    (comp (ref "C219")
      (value "GRM033R60J104KE19D")
      (footprint "CAPC0603X33X15LL03T05")
      (description "Chip Capacitor, 100 nF, +/- 10%, 6.3 V, -55 to 85 degC, 0201 (0603 Metric), RoHS, Tape and Reel")
      (fields (field (name "TOLERANCE") "10%") (field (name "MANUFACTURER") "Basic Passives"))
      (libsource (lib "MiniPC DB") (part "CAP_NP"))
    )
    (comp (ref "C220")
      (value "GRM033R60J104KE19D")
      (footprint "CAPC0603X33X15LL03T05")
      (description "Chip Capacitor, 100 nF, +/- 10%, 6.3 V, -55 to 85 degC, 0201 (0603 Metric), RoHS, Tape and Reel")
      (fields (field (name "TOLERANCE") "10%") (field (name "MANUFACTURER") "Basic Passives"))
      (libsource (lib "MiniPC DB") (part "CAP_NP"))
    )
    (comp (ref "C221")
      (value "GRM033R60J104KE19D")
      (footprint "CAPC0603X33X15LL03T05")
      (description "Chip Capacitor, 100 nF, +/- 10%, 6.3 V, -55 to 85 degC, 0201 (0603 Metric), RoHS, Tape and Reel")
      (fields (field (name "TOLERANCE") "10%") (field (name "MANUFACTURER") "Basic Passives"))
      (libsource (lib "MiniPC DB") (part "CAP_NP"))
    )
    (comp (ref "C222")
      (value "GRM033R60J104KE19D")
      (footprint "CAPC0603X33X15LL03T05")
      (description "Chip Capacitor, 100 nF, +/- 10%, 6.3 V, -55 to 85 degC, 0201 (0603 Metric), RoHS, Tape and Reel")
      (fields (field (name "TOLERANCE") "10%") (field (name "MANUFACTURER") "Basic Passives"))
      (libsource (lib "MiniPC DB") (part "CAP_NP"))
    )
    (comp (ref "C223")
      (value "GRM033R60J104KE19D")
      (footprint "CAPC0603X33X15LL03T05")
      (description "Chip Capacitor, 100 nF, +/- 10%, 6.3 V, -55 to 85 degC, 0201 (0603 Metric), RoHS, Tape and Reel")
      (fields (field (name "TOLERANCE") "10%") (field (name "MANUFACTURER") "Basic Passives"))
      (libsource (lib "MiniPC DB") (part "CAP_NP"))
    )
    (comp (ref "C224")
      (value "GRM033R60J104KE19D")
      (footprint "CAPC0603X33X15LL03T05")
      (description "Chip Capacitor, 100 nF, +/- 10%, 6.3 V, -55 to 85 degC, 0201 (0603 Metric), RoHS, Tape and Reel")
      (fields (field (name "TOLERANCE") "10%") (field (name "MANUFACTURER") "Basic Passives"))
      (libsource (lib "MiniPC DB") (part "CAP_NP"))
    )
    (comp (ref "C225")
      (value "GRM033R60J104KE19D")
      (footprint "CAPC0603X33X15LL03T05")
      (description "Chip Capacitor, 100 nF, +/- 10%, 6.3 V, -55 to 85 degC, 0201 (0603 Metric), RoHS, Tape and Reel")
      (fields (field (name "TOLERANCE") "10%") (field (name "MANUFACTURER") "Basic Passives"))
      (libsource (lib "MiniPC DB") (part "CAP_NP"))
    )
    (comp (ref "C226")
      (value "GRM033R60J104KE19D")
      (footprint "CAPC0603X33X15LL03T05")
      (description "Chip Capacitor, 100 nF, +/- 10%, 6.3 V, -55 to 85 degC, 0201 (0603 Metric), RoHS, Tape and Reel")
      (fields (field (name "TOLERANCE") "10%") (field (name "MANUFACTURER") "Basic Passives"))
      (libsource (lib "MiniPC DB") (part "CAP_NP"))
    )
    (comp (ref "C227")
      (value "GRM033R60J104KE19D")
      (footprint "CAPC0603X33X15LL03T05")
      (description "Chip Capacitor, 100 nF, +/- 10%, 6.3 V, -55 to 85 degC, 0201 (0603 Metric), RoHS, Tape and Reel")
      (fields (field (name "TOLERANCE") "10%") (field (name "MANUFACTURER") "Basic Passives"))
      (libsource (lib "MiniPC DB") (part "CAP_NP"))
    )
    (comp (ref "C228")
      (value "GRM033R60J104KE19D")
      (footprint "CAPC0603X33X15LL03T05")
      (description "Chip Capacitor, 100 nF, +/- 10%, 6.3 V, -55 to 85 degC, 0201 (0603 Metric), RoHS, Tape and Reel")
      (fields (field (name "TOLERANCE") "10%") (field (name "MANUFACTURER") "Basic Passives"))
      (libsource (lib "MiniPC DB") (part "CAP_NP"))
    )
    (comp (ref "C229")
      (value "GRM033R60J104KE19D")
      (footprint "CAPC0603X33X15LL03T05")
      (description "Chip Capacitor, 100 nF, +/- 10%, 6.3 V, -55 to 85 degC, 0201 (0603 Metric), RoHS, Tape and Reel")
      (fields (field (name "TOLERANCE") "10%") (field (name "MANUFACTURER") "Basic Passives"))
      (libsource (lib "MiniPC DB") (part "CAP_NP"))
    )
  )
  (nets
    (net (code "1") (name "/0V95") (class "Default")
      (node (ref "C109") (pin "2") (pinfunction "2_2") (pintype "passive"))
      (node (ref "C119") (pin "2") (pinfunction "2_2") (pintype "passive"))
      (node (ref "C131") (pin "2") (pinfunction "2_2") (pintype "passive"))
      (node (ref "C143") (pin "2") (pinfunction "2_2") (pintype "passive"))
      (node (ref "C155") (pin "2") (pinfunction "2_2") (pintype "passive"))
      (node (ref "C166") (pin "2") (pinfunction "2_2") (pintype "passive"))
      (node (ref "C177") (pin "2") (pinfunction "2_2") (pintype "passive"))
    )
    (net (code "2") (name "/Core_0V9") (class "Default")
      (node (ref "C100") (pin "2") (pinfunction "2_2") (pintype "passive"))
      (node (ref "C101") (pin "2") (pinfunction "2_2") (pintype "passive"))
      (node (ref "C102") (pin "2") (pinfunction "2_2") (pintype "passive"))
      (node (ref "C103") (pin "2") (pinfunction "2_2") (pintype "passive"))
      (node (ref "C104") (pin "2") (pinfunction "2_2") (pintype "passive"))
      (node (ref "C105") (pin "2") (pinfunction "2_2") (pintype "passive"))
      (node (ref "C106") (pin "2") (pinfunction "2_2") (pintype "passive"))
      (node (ref "C107") (pin "2") (pinfunction "2_2") (pintype "passive"))
      (node (ref "C110") (pin "2") (pinfunction "2_2") (pintype "passive"))
      (node (ref "C111") (pin "2") (pinfunction "2_2") (pintype "passive"))
      (node (ref "C112") (pin "2") (pinfunction "2_2") (pintype "passive"))
      (node (ref "C113") (pin "2") (pinfunction "2_2") (pintype "passive"))
      (node (ref "C114") (pin "2") (pinfunction "2_2") (pintype "passive"))
      (node (ref "C115") (pin "2") (pinfunction "2_2") (pintype "passive"))
      (node (ref "C116") (pin "2") (pinfunction "2_2") (pintype "passive"))
      (node (ref "C117") (pin "2") (pinfunction "2_2") (pintype "passive"))
      (node (ref "C120") (pin "2") (pinfunction "2_2") (pintype "passive"))
      (node (ref "C121") (pin "2") (pinfunction "2_2") (pintype "passive"))
      (node (ref "C122") (pin "2") (pinfunction "2_2") (pintype "passive"))
      (node (ref "C123") (pin "2") (pinfunction "2_2") (pintype "passive"))
      (node (ref "C124") (pin "2") (pinfunction "2_2") (pintype "passive"))
      (node (ref "C125") (pin "2") (pinfunction "2_2") (pintype "passive"))
      (node (ref "C126") (pin "2") (pinfunction "2_2") (pintype "passive"))
      (node (ref "C127") (pin "2") (pinfunction "2_2") (pintype "passive"))
      (node (ref "C128") (pin "2") (pinfunction "2_2") (pintype "passive"))
      (node (ref "C129") (pin "2") (pinfunction "2_2") (pintype "passive"))
      (node (ref "C132") (pin "2") (pinfunction "2_2") (pintype "passive"))
      (node (ref "C133") (pin "2") (pinfunction "2_2") (pintype "passive"))
      (node (ref "C134") (pin "2") (pinfunction "2_2") (pintype "passive"))
      (node (ref "C135") (pin "2") (pinfunction "2_2") (pintype "passive"))
      (node (ref "C136") (pin "2") (pinfunction "2_2") (pintype "passive"))
      (node (ref "C137") (pin "2") (pinfunction "2_2") (pintype "passive"))
      (node (ref "C138") (pin "2") (pinfunction "2_2") (pintype "passive"))
      (node (ref "C139") (pin "2") (pinfunction "2_2") (pintype "passive"))
      (node (ref "C140") (pin "2") (pinfunction "2_2") (pintype "passive"))
      (node (ref "C141") (pin "2") (pinfunction "2_2") (pintype "passive"))
      (node (ref "C144") (pin "2") (pinfunction "2_2") (pintype "passive"))
      (node (ref "C145") (pin "2") (pinfunction "2_2") (pintype "passive"))
      (node (ref "C146") (pin "2") (pinfunction "2_2") (pintype "passive"))
      (node (ref "C147") (pin "2") (pinfunction "2_2") (pintype "passive"))
      (node (ref "C148") (pin "2") (pinfunction "2_2") (pintype "passive"))
      (node (ref "C149") (pin "2") (pinfunction "2_2") (pintype "passive"))
      (node (ref "C150") (pin "2") (pinfunction "2_2") (pintype "passive"))
      (node (ref "C151") (pin "2") (pinfunction "2_2") (pintype "passive"))
      (node (ref "C152") (pin "2") (pinfunction "2_2") (pintype "passive"))
      (node (ref "C153") (pin "2") (pinfunction "2_2") (pintype "passive"))
      (node (ref "C156") (pin "2") (pinfunction "2_2") (pintype "passive"))
      (node (ref "C157") (pin "2") (pinfunction "2_2") (pintype "passive"))
      (node (ref "C158") (pin "2") (pinfunction "2_2") (pintype "passive"))
      (node (ref "C159") (pin "2") (pinfunction "2_2") (pintype "passive"))
      (node (ref "C160") (pin "2") (pinfunction "2_2") (pintype "passive"))
      (node (ref "C161") (pin "2") (pinfunction "2_2") (pintype "passive"))
      (node (ref "C162") (pin "2") (pinfunction "2_2") (pintype "passive"))
      (node (ref "C163") (pin "2") (pinfunction "2_2") (pintype "passive"))
      (node (ref "C164") (pin "2") (pinfunction "2_2") (pintype "passive"))
      (node (ref "C165") (pin "2") (pinfunction "2_2") (pintype "passive"))
      (node (ref "C167") (pin "2") (pinfunction "2_2") (pintype "passive"))
      (node (ref "C168") (pin "2") (pinfunction "2_2") (pintype "passive"))
      (node (ref "C169") (pin "2") (pinfunction "2_2") (pintype "passive"))
      (node (ref "C170") (pin "2") (pinfunction "2_2") (pintype "passive"))
      (node (ref "C171") (pin "2") (pinfunction "2_2") (pintype "passive"))
      (node (ref "C172") (pin "2") (pinfunction "2_2") (pintype "passive"))
      (node (ref "C173") (pin "2") (pinfunction "2_2") (pintype "passive"))
      (node (ref "C174") (pin "2") (pinfunction "2_2") (pintype "passive"))
      (node (ref "C175") (pin "2") (pinfunction "2_2") (pintype "passive"))
      (node (ref "C176") (pin "2") (pinfunction "2_2") (pintype "passive"))
      (node (ref "C178") (pin "2") (pinfunction "2_2") (pintype "passive"))
      (node (ref "C179") (pin "2") (pinfunction "2_2") (pintype "passive"))
      (node (ref "C180") (pin "2") (pinfunction "2_2") (pintype "passive"))
      (node (ref "C181") (pin "2") (pinfunction "2_2") (pintype "passive"))
      (node (ref "C182") (pin "2") (pinfunction "2_2") (pintype "passive"))
      (node (ref "C183") (pin "2") (pinfunction "2_2") (pintype "passive"))
      (node (ref "C184") (pin "2") (pinfunction "2_2") (pintype "passive"))
      (node (ref "C185") (pin "2") (pinfunction "2_2") (pintype "passive"))
      (node (ref "C186") (pin "2") (pinfunction "2_2") (pintype "passive"))
      (node (ref "C187") (pin "2") (pinfunction "2_2") (pintype "passive"))
      (node (ref "C188") (pin "2") (pinfunction "2_2") (pintype "passive"))
      (node (ref "C189") (pin "2") (pinfunction "2_2") (pintype "passive"))
      (node (ref "C190") (pin "2") (pinfunction "2_2") (pintype "passive"))
      (node (ref "C191") (pin "2") (pinfunction "2_2") (pintype "passive"))
      (node (ref "C192") (pin "2") (pinfunction "2_2") (pintype "passive"))
      (node (ref "C193") (pin "2") (pinfunction "2_2") (pintype "passive"))
      (node (ref "C194") (pin "2") (pinfunction "2_2") (pintype "passive"))
      (node (ref "C195") (pin "2") (pinfunction "2_2") (pintype "passive"))
      (node (ref "C196") (pin "2") (pinfunction "2_2") (pintype "passive"))
      (node (ref "C197") (pin "2") (pinfunction "2_2") (pintype "passive"))
      (node (ref "C198") (pin "2") (pinfunction "2_2") (pintype "passive"))
      (node (ref "C199") (pin "2") (pinfunction "2_2") (pintype "passive"))
      (node (ref "C200") (pin "2") (pinfunction "2_2") (pintype "passive"))
      (node (ref "C201") (pin "2") (pinfunction "2_2") (pintype "passive"))
      (node (ref "C202") (pin "2") (pinfunction "2_2") (pintype "passive"))
      (node (ref "C203") (pin "2") (pinfunction "2_2") (pintype "passive"))
      (node (ref "C204") (pin "2") (pinfunction "2_2") (pintype "passive"))
      (node (ref "C205") (pin "2") (pinfunction "2_2") (pintype "passive"))
      (node (ref "C206") (pin "2") (pinfunction "2_2") (pintype "passive"))
      (node (ref "C207") (pin "2") (pinfunction "2_2") (pintype "passive"))
      (node (ref "C208") (pin "2") (pinfunction "2_2") (pintype "passive"))
      (node (ref "C209") (pin "2") (pinfunction "2_2") (pintype "passive"))
      (node (ref "C210") (pin "2") (pinfunction "2_2") (pintype "passive"))
      (node (ref "C211") (pin "2") (pinfunction "2_2") (pintype "passive"))
      (node (ref "C212") (pin "2") (pinfunction "2_2") (pintype "passive"))
      (node (ref "C213") (pin "2") (pinfunction "2_2") (pintype "passive"))
      (node (ref "C214") (pin "2") (pinfunction "2_2") (pintype "passive"))
      (node (ref "C215") (pin "2") (pinfunction "2_2") (pintype "passive"))
      (node (ref "C216") (pin "2") (pinfunction "2_2") (pintype "passive"))
      (node (ref "C217") (pin "2") (pinfunction "2_2") (pintype "passive"))
      (node (ref "C218") (pin "2") (pinfunction "2_2") (pintype "passive"))
      (node (ref "C219") (pin "2") (pinfunction "2_2") (pintype "passive"))
      (node (ref "C220") (pin "2") (pinfunction "2_2") (pintype "passive"))
      (node (ref "C221") (pin "2") (pinfunction "2_2") (pintype "passive"))
      (node (ref "C222") (pin "2") (pinfunction "2_2") (pintype "passive"))
      (node (ref "C223") (pin "2") (pinfunction "2_2") (pintype "passive"))
      (node (ref "C224") (pin "2") (pinfunction "2_2") (pintype "passive"))
      (node (ref "C225") (pin "2") (pinfunction "2_2") (pintype "passive"))
      (node (ref "C226") (pin "2") (pinfunction "2_2") (pintype "passive"))
      (node (ref "C227") (pin "2") (pinfunction "2_2") (pintype "passive"))
      (node (ref "C228") (pin "2") (pinfunction "2_2") (pintype "passive"))
      (node (ref "C229") (pin "2") (pinfunction "2_2") (pintype "passive"))
      (node (ref "C98") (pin "2") (pinfunction "2_2") (pintype "passive"))
      (node (ref "C99") (pin "2") (pinfunction "2_2") (pintype "passive"))
    )
    (net (code "3") (name "/HPS_0V95") (class "Default")
      (node (ref "C108") (pin "2") (pinfunction "2_2") (pintype "passive"))
      (node (ref "C118") (pin "2") (pinfunction "2_2") (pintype "passive"))
      (node (ref "C130") (pin "2") (pinfunction "2_2") (pintype "passive"))
      (node (ref "C142") (pin "2") (pinfunction "2_2") (pintype "passive"))
      (node (ref "C154") (pin "2") (pinfunction "2_2") (pintype "passive"))
    )
    (net (code "4") (name "GND") (class "Default")
      (node (ref "C100") (pin "1") (pinfunction "1_1") (pintype "passive"))
      (node (ref "C101") (pin "1") (pinfunction "1_1") (pintype "passive"))
      (node (ref "C102") (pin "1") (pinfunction "1_1") (pintype "passive"))
      (node (ref "C103") (pin "1") (pinfunction "1_1") (pintype "passive"))
      (node (ref "C104") (pin "1") (pinfunction "1_1") (pintype "passive"))
      (node (ref "C105") (pin "1") (pinfunction "1_1") (pintype "passive"))
      (node (ref "C106") (pin "1") (pinfunction "1_1") (pintype "passive"))
      (node (ref "C107") (pin "1") (pinfunction "1_1") (pintype "passive"))
      (node (ref "C108") (pin "1") (pinfunction "1_1") (pintype "passive"))
      (node (ref "C109") (pin "1") (pinfunction "1_1") (pintype "passive"))
      (node (ref "C110") (pin "1") (pinfunction "1_1") (pintype "passive"))
      (node (ref "C111") (pin "1") (pinfunction "1_1") (pintype "passive"))
      (node (ref "C112") (pin "1") (pinfunction "1_1") (pintype "passive"))
      (node (ref "C113") (pin "1") (pinfunction "1_1") (pintype "passive"))
      (node (ref "C114") (pin "1") (pinfunction "1_1") (pintype "passive"))
      (node (ref "C115") (pin "1") (pinfunction "1_1") (pintype "passive"))
      (node (ref "C116") (pin "1") (pinfunction "1_1") (pintype "passive"))
      (node (ref "C117") (pin "1") (pinfunction "1_1") (pintype "passive"))
      (node (ref "C118") (pin "1") (pinfunction "1_1") (pintype "passive"))
      (node (ref "C119") (pin "1") (pinfunction "1_1") (pintype "passive"))
      (node (ref "C120") (pin "1") (pinfunction "1_1") (pintype "passive"))
      (node (ref "C121") (pin "1") (pinfunction "1_1") (pintype "passive"))
      (node (ref "C122") (pin "1") (pinfunction "1_1") (pintype "passive"))
      (node (ref "C123") (pin "1") (pinfunction "1_1") (pintype "passive"))
      (node (ref "C124") (pin "1") (pinfunction "1_1") (pintype "passive"))
      (node (ref "C125") (pin "1") (pinfunction "1_1") (pintype "passive"))
      (node (ref "C126") (pin "1") (pinfunction "1_1") (pintype "passive"))
      (node (ref "C127") (pin "1") (pinfunction "1_1") (pintype "passive"))
      (node (ref "C128") (pin "1") (pinfunction "1_1") (pintype "passive"))
      (node (ref "C129") (pin "1") (pinfunction "1_1") (pintype "passive"))
      (node (ref "C130") (pin "1") (pinfunction "1_1") (pintype "passive"))
      (node (ref "C131") (pin "1") (pinfunction "1_1") (pintype "passive"))
      (node (ref "C132") (pin "1") (pinfunction "1_1") (pintype "passive"))
      (node (ref "C133") (pin "1") (pinfunction "1_1") (pintype "passive"))
      (node (ref "C134") (pin "1") (pinfunction "1_1") (pintype "passive"))
      (node (ref "C135") (pin "1") (pinfunction "1_1") (pintype "passive"))
      (node (ref "C136") (pin "1") (pinfunction "1_1") (pintype "passive"))
      (node (ref "C137") (pin "1") (pinfunction "1_1") (pintype "passive"))
      (node (ref "C138") (pin "1") (pinfunction "1_1") (pintype "passive"))
      (node (ref "C139") (pin "1") (pinfunction "1_1") (pintype "passive"))
      (node (ref "C140") (pin "1") (pinfunction "1_1") (pintype "passive"))
      (node (ref "C141") (pin "1") (pinfunction "1_1") (pintype "passive"))
      (node (ref "C142") (pin "1") (pinfunction "1_1") (pintype "passive"))
      (node (ref "C143") (pin "1") (pinfunction "1_1") (pintype "passive"))
      (node (ref "C144") (pin "1") (pinfunction "1_1") (pintype "passive"))
      (node (ref "C145") (pin "1") (pinfunction "1_1") (pintype "passive"))
      (node (ref "C146") (pin "1") (pinfunction "1_1") (pintype "passive"))
      (node (ref "C147") (pin "1") (pinfunction "1_1") (pintype "passive"))
      (node (ref "C148") (pin "1") (pinfunction "1_1") (pintype "passive"))
      (node (ref "C149") (pin "1") (pinfunction "1_1") (pintype "passive"))
      (node (ref "C150") (pin "1") (pinfunction "1_1") (pintype "passive"))
      (node (ref "C151") (pin "1") (pinfunction "1_1") (pintype "passive"))
      (node (ref "C152") (pin "1") (pinfunction "1_1") (pintype "passive"))
      (node (ref "C153") (pin "1") (pinfunction "1_1") (pintype "passive"))
      (node (ref "C154") (pin "1") (pinfunction "1_1") (pintype "passive"))
      (node (ref "C155") (pin "1") (pinfunction "1_1") (pintype "passive"))
      (node (ref "C156") (pin "1") (pinfunction "1_1") (pintype "passive"))
      (node (ref "C157") (pin "1") (pinfunction "1_1") (pintype "passive"))
      (node (ref "C158") (pin "1") (pinfunction "1_1") (pintype "passive"))
      (node (ref "C159") (pin "1") (pinfunction "1_1") (pintype "passive"))
      (node (ref "C160") (pin "1") (pinfunction "1_1") (pintype "passive"))
      (node (ref "C161") (pin "1") (pinfunction "1_1") (pintype "passive"))
      (node (ref "C162") (pin "1") (pinfunction "1_1") (pintype "passive"))
      (node (ref "C163") (pin "1") (pinfunction "1_1") (pintype "passive"))
      (node (ref "C164") (pin "1") (pinfunction "1_1") (pintype "passive"))
      (node (ref "C165") (pin "1") (pinfunction "1_1") (pintype "passive"))
      (node (ref "C166") (pin "1") (pinfunction "1_1") (pintype "passive"))
      (node (ref "C167") (pin "1") (pinfunction "1_1") (pintype "passive"))
      (node (ref "C168") (pin "1") (pinfunction "1_1") (pintype "passive"))
      (node (ref "C169") (pin "1") (pinfunction "1_1") (pintype "passive"))
      (node (ref "C170") (pin "1") (pinfunction "1_1") (pintype "passive"))
      (node (ref "C171") (pin "1") (pinfunction "1_1") (pintype "passive"))
      (node (ref "C172") (pin "1") (pinfunction "1_1") (pintype "passive"))
      (node (ref "C173") (pin "1") (pinfunction "1_1") (pintype "passive"))
      (node (ref "C174") (pin "1") (pinfunction "1_1") (pintype "passive"))
      (node (ref "C175") (pin "1") (pinfunction "1_1") (pintype "passive"))
      (node (ref "C176") (pin "1") (pinfunction "1_1") (pintype "passive"))
      (node (ref "C177") (pin "1") (pinfunction "1_1") (pintype "passive"))
      (node (ref "C178") (pin "1") (pinfunction "1_1") (pintype "passive"))
      (node (ref "C179") (pin "1") (pinfunction "1_1") (pintype "passive"))
      (node (ref "C180") (pin "1") (pinfunction "1_1") (pintype "passive"))
      (node (ref "C181") (pin "1") (pinfunction "1_1") (pintype "passive"))
      (node (ref "C182") (pin "1") (pinfunction "1_1") (pintype "passive"))
      (node (ref "C183") (pin "1") (pinfunction "1_1") (pintype "passive"))
      (node (ref "C184") (pin "1") (pinfunction "1_1") (pintype "passive"))
      (node (ref "C185") (pin "1") (pinfunction "1_1") (pintype "passive"))
      (node (ref "C186") (pin "1") (pinfunction "1_1") (pintype "passive"))
      (node (ref "C187") (pin "1") (pinfunction "1_1") (pintype "passive"))
      (node (ref "C188") (pin "1") (pinfunction "1_1") (pintype "passive"))
      (node (ref "C189") (pin "1") (pinfunction "1_1") (pintype "passive"))
      (node (ref "C190") (pin "1") (pinfunction "1_1") (pintype "passive"))
      (node (ref "C191") (pin "1") (pinfunction "1_1") (pintype "passive"))
      (node (ref "C192") (pin "1") (pinfunction "1_1") (pintype "passive"))
      (node (ref "C193") (pin "1") (pinfunction "1_1") (pintype "passive"))
      (node (ref "C194") (pin "1") (pinfunction "1_1") (pintype "passive"))
      (node (ref "C195") (pin "1") (pinfunction "1_1") (pintype "passive"))
      (node (ref "C196") (pin "1") (pinfunction "1_1") (pintype "passive"))
      (node (ref "C197") (pin "1") (pinfunction "1_1") (pintype "passive"))
      (node (ref "C198") (pin "1") (pinfunction "1_1") (pintype "passive"))
      (node (ref "C199") (pin "1") (pinfunction "1_1") (pintype "passive"))
      (node (ref "C200") (pin "1") (pinfunction "1_1") (pintype "passive"))
      (node (ref "C201") (pin "1") (pinfunction "1_1") (pintype "passive"))
      (node (ref "C202") (pin "1") (pinfunction "1_1") (pintype "passive"))
      (node (ref "C203") (pin "1") (pinfunction "1_1") (pintype "passive"))
      (node (ref "C204") (pin "1") (pinfunction "1_1") (pintype "passive"))
      (node (ref "C205") (pin "1") (pinfunction "1_1") (pintype "passive"))
      (node (ref "C206") (pin "1") (pinfunction "1_1") (pintype "passive"))
      (node (ref "C207") (pin "1") (pinfunction "1_1") (pintype "passive"))
      (node (ref "C208") (pin "1") (pinfunction "1_1") (pintype "passive"))
      (node (ref "C209") (pin "1") (pinfunction "1_1") (pintype "passive"))
      (node (ref "C210") (pin "1") (pinfunction "1_1") (pintype "passive"))
      (node (ref "C211") (pin "1") (pinfunction "1_1") (pintype "passive"))
      (node (ref "C212") (pin "1") (pinfunction "1_1") (pintype "passive"))
      (node (ref "C213") (pin "1") (pinfunction "1_1") (pintype "passive"))
      (node (ref "C214") (pin "1") (pinfunction "1_1") (pintype "passive"))
      (node (ref "C215") (pin "1") (pinfunction "1_1") (pintype "passive"))
      (node (ref "C216") (pin "1") (pinfunction "1_1") (pintype "passive"))
      (node (ref "C217") (pin "1") (pinfunction "1_1") (pintype "passive"))
      (node (ref "C218") (pin "1") (pinfunction "1_1") (pintype "passive"))
      (node (ref "C219") (pin "1") (pinfunction "1_1") (pintype "passive"))
      (node (ref "C220") (pin "1") (pinfunction "1_1") (pintype "passive"))
      (node (ref "C221") (pin "1") (pinfunction "1_1") (pintype "passive"))
      (node (ref "C222") (pin "1") (pinfunction "1_1") (pintype "passive"))
      (node (ref "C223") (pin "1") (pinfunction "1_1") (pintype "passive"))
      (node (ref "C224") (pin "1") (pinfunction "1_1") (pintype "passive"))
      (node (ref "C225") (pin "1") (pinfunction "1_1") (pintype "passive"))
      (node (ref "C226") (pin "1") (pinfunction "1_1") (pintype "passive"))
      (node (ref "C227") (pin "1") (pinfunction "1_1") (pintype "passive"))
      (node (ref "C228") (pin "1") (pinfunction "1_1") (pintype "passive"))
      (node (ref "C229") (pin "1") (pinfunction "1_1") (pintype "passive"))
      (node (ref "C98") (pin "1") (pinfunction "1_1") (pintype "passive"))
      (node (ref "C99") (pin "1") (pinfunction "1_1") (pintype "passive"))
    )
  )
)
